# cpu_base.net
KiCad netlist of a schematic drawn in EAGLE
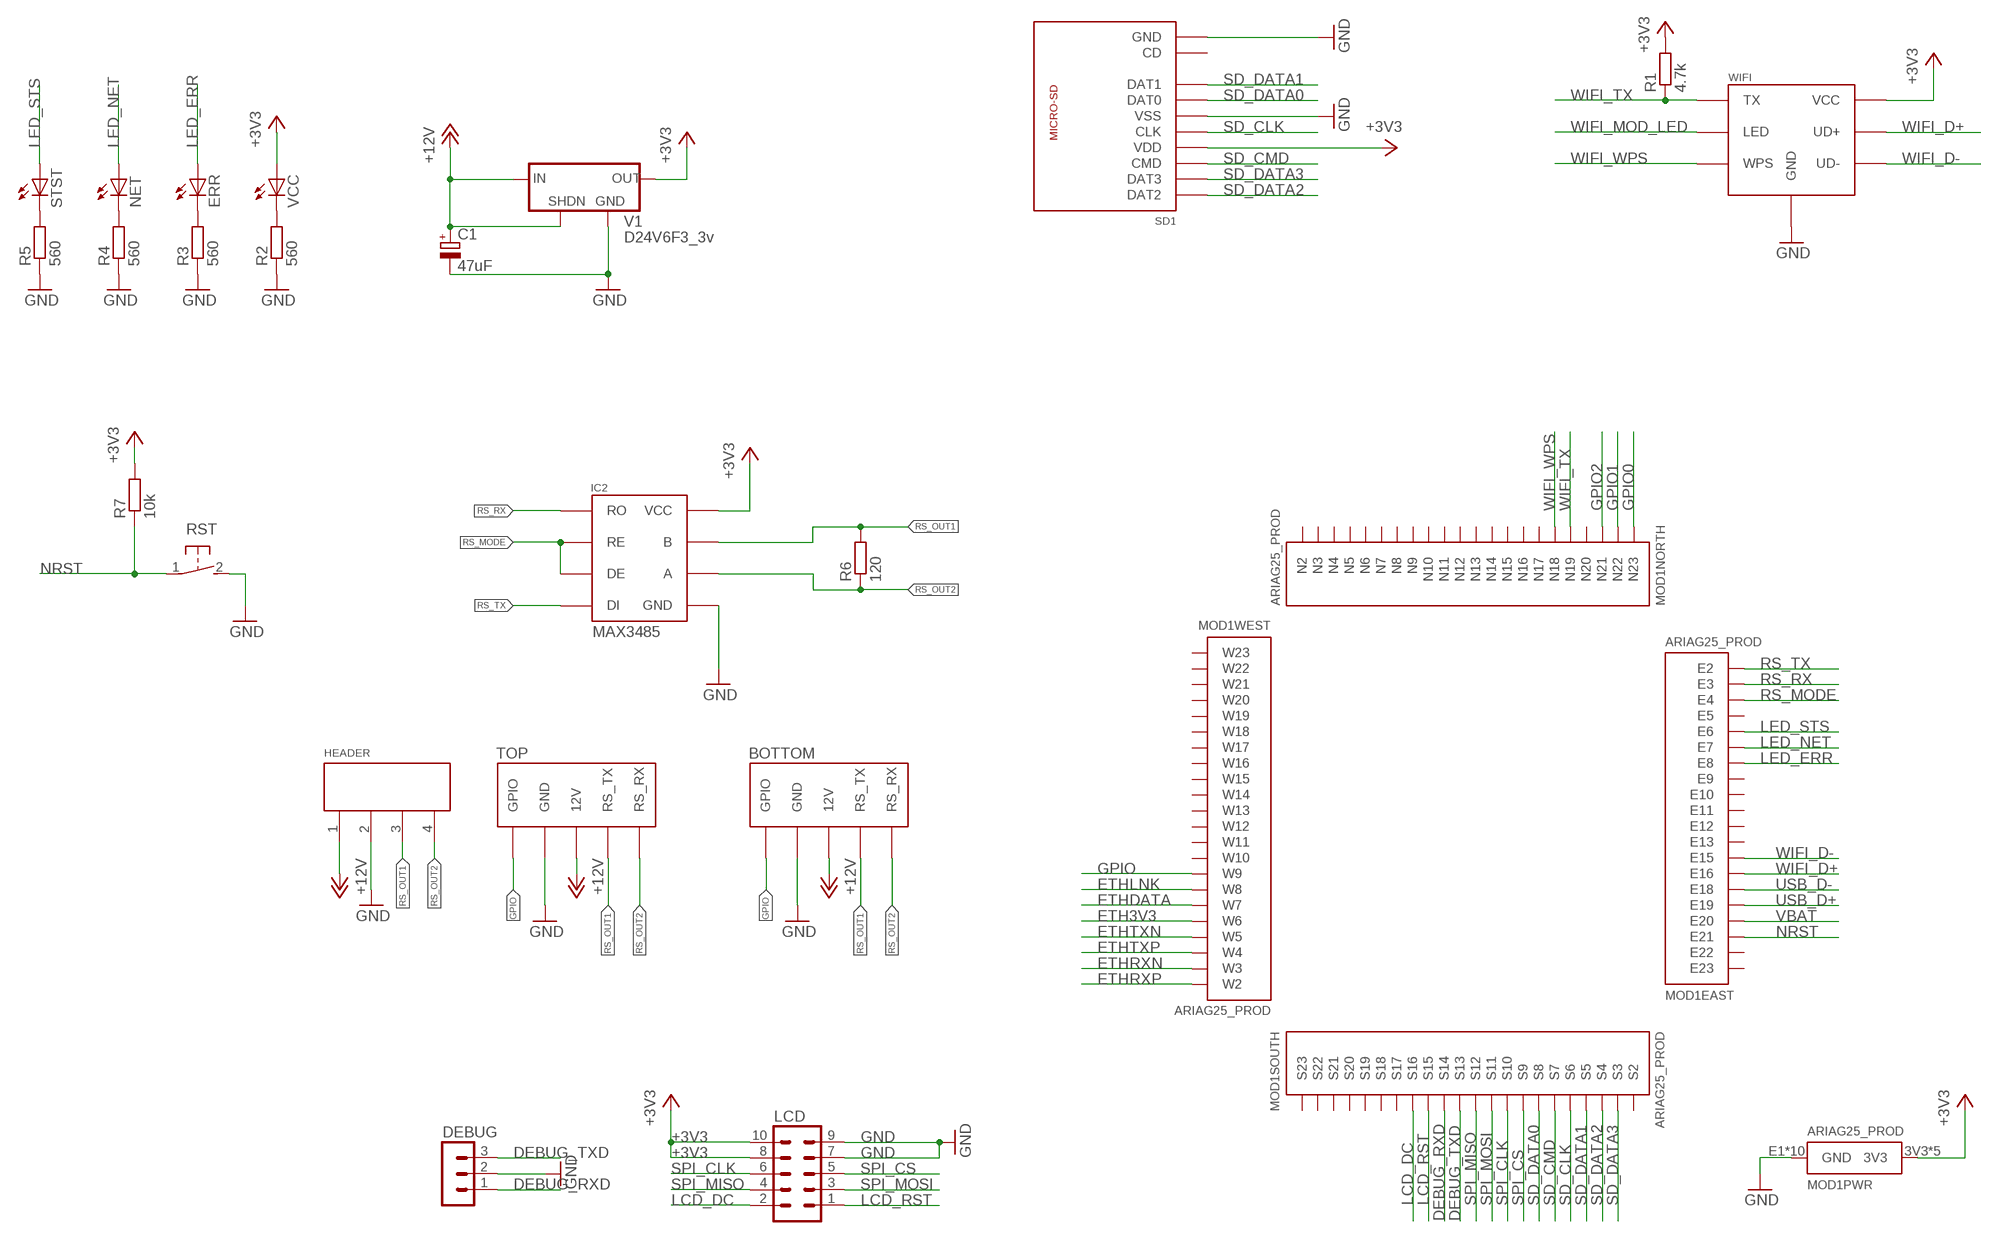
[diagram p0: schematic, sheet 1]

(export (version "E")
  (design (tool "Eeschema 10.0.6"))
  (components
    (comp (ref "BOTTOM")
      (value "STEROWNIK-PINY_5PIN_BOTTOM")
      (footprint "eagle-import:STEROWNIK-PINY_5PIN_BOTTOM")
      (libsource (lib "eagle-import") (part "STEROWNIK-PINY_5PIN_BOTTOM"))
    )
    (comp (ref "C1")
      (value "47uF")
      (footprint "eagle-import:153CLV-0810")
      (libsource (lib "eagle-import") (part "CPOL-EU153CLV-0810"))
    )
    (comp (ref "DEBUG")
      (value "MA03-1")
      (footprint "eagle-import:MA03-1")
      (libsource (lib "eagle-import") (part "MA03-1"))
    )
    (comp (ref "ERR")
      (value "LEDCHIPLED_0805")
      (footprint "eagle-import:CHIPLED_0805")
      (libsource (lib "eagle-import") (part "LEDCHIPLED_0805"))
    )
    (comp (ref "HEADER")
      (value "TBMP5104RO-KF")
      (footprint "eagle-import:TBMP5104RO-KF")
      (libsource (lib "eagle-import") (part "TBMP5104RO-KF"))
    )
    (comp (ref "IC2")
      (value "MAX3485")
      (footprint "eagle-import:SO-8")
      (libsource (lib "eagle-import") (part "MAX3485"))
    )
    (comp (ref "LCD")
      (value "MA05-2")
      (footprint "eagle-import:MA05-2")
      (libsource (lib "eagle-import") (part "MA05-2"))
    )
    (comp (ref "MOD1")
      (value "ARIAG25_PROD")
      (footprint "eagle-import:G25_D")
      (libsource (lib "eagle-import") (part "ARIAG25_PROD"))
    )
    (comp (ref "NET")
      (value "LEDCHIPLED_0805")
      (footprint "eagle-import:CHIPLED_0805")
      (libsource (lib "eagle-import") (part "LEDCHIPLED_0805"))
    )
    (comp (ref "R1")
      (value "4.7k")
      (footprint "eagle-import:R0805")
      (libsource (lib "eagle-import") (part "R-EU_R0805"))
    )
    (comp (ref "R2")
      (value "560")
      (footprint "eagle-import:R0805")
      (libsource (lib "eagle-import") (part "R-EU_R0805"))
    )
    (comp (ref "R3")
      (value "560")
      (footprint "eagle-import:R0805")
      (libsource (lib "eagle-import") (part "R-EU_R0805"))
    )
    (comp (ref "R4")
      (value "560")
      (footprint "eagle-import:R0805")
      (libsource (lib "eagle-import") (part "R-EU_R0805"))
    )
    (comp (ref "R5")
      (value "560")
      (footprint "eagle-import:R0805")
      (libsource (lib "eagle-import") (part "R-EU_R0805"))
    )
    (comp (ref "R6")
      (value "120")
      (footprint "eagle-import:R0805")
      (libsource (lib "eagle-import") (part "R-EU_R0805"))
    )
    (comp (ref "R7")
      (value "10k")
      (footprint "eagle-import:R0805")
      (libsource (lib "eagle-import") (part "R-EU_R0805"))
    )
    (comp (ref "RST")
      (value "31-XX")
      (footprint "eagle-import:B3F-31XX")
      (fields (field (name "MPN") "B3F-3100"))
      (libsource (lib "eagle-import") (part "31-XX"))
    )
    (comp (ref "SD1")
      (value "MICRO-SD")
      (footprint "eagle-import:112I-TDAR-R")
      (libsource (lib "eagle-import") (part "MICRO-SD"))
    )
    (comp (ref "STST")
      (value "LEDCHIPLED_0805")
      (footprint "eagle-import:CHIPLED_0805")
      (libsource (lib "eagle-import") (part "LEDCHIPLED_0805"))
    )
    (comp (ref "TOP")
      (value "STEROWNIK-PINY_5PIN")
      (footprint "eagle-import:STEROWNIK-PINY_5PIN")
      (libsource (lib "eagle-import") (part "STEROWNIK-PINY_5PIN"))
    )
    (comp (ref "V1")
      (value "D24V6F3_3v")
      (footprint "eagle-import:D24V6F5_5V")
      (libsource (lib "eagle-import") (part "D24V6F5_5V"))
    )
    (comp (ref "VCC")
      (value "LEDCHIPLED_0805")
      (footprint "eagle-import:CHIPLED_0805")
      (libsource (lib "eagle-import") (part "LEDCHIPLED_0805"))
    )
    (comp (ref "WIFI")
      (value "WIFI-2-OEM")
      (footprint "eagle-import:WIFI")
      (libsource (lib "eagle-import") (part "WIFI-2-OEM"))
    )
  )
  (nets
    (net (code "1") (name "+3V3") (class "Default")
      (node (ref "IC2") (pin "VCC") (pinfunction "VCC_VCC") (pintype "bidirectional"))
      (node (ref "LCD") (pin "10") (pinfunction "10_10") (pintype "passive"))
      (node (ref "LCD") (pin "8") (pinfunction "8_8") (pintype "passive"))
      (node (ref "MOD1") (pin "3V3") (pinfunction "3V3_3V3") (pintype "power_in"))
      (node (ref "MOD1") (pin "E24") (pinfunction "3V3_E24") (pintype "power_in"))
      (node (ref "MOD1") (pin "N1") (pinfunction "3V3_N1") (pintype "power_in"))
      (node (ref "MOD1") (pin "S1") (pinfunction "3V3_S1") (pintype "power_in"))
      (node (ref "MOD1") (pin "W24") (pinfunction "3V3_W24") (pintype "power_in"))
      (node (ref "R1") (pin "2") (pinfunction "2_2") (pintype "passive"))
      (node (ref "R7") (pin "2") (pinfunction "2_2") (pintype "passive"))
      (node (ref "SD1") (pin "4") (pinfunction "VDD_4") (pintype "bidirectional"))
      (node (ref "V1") (pin "VOUT") (pinfunction "OUT_VOUT") (pintype "passive"))
      (node (ref "VCC") (pin "A") (pinfunction "A_A") (pintype "passive"))
      (node (ref "WIFI") (pin "VCC") (pinfunction "VCC_VCC") (pintype "bidirectional"))
    )
    (net (code "2") (name "+12V") (class "Default")
      (node (ref "BOTTOM") (pin "12") (pinfunction "12V_12") (pintype "bidirectional"))
      (node (ref "C1") (pin "+") (pinfunction "+_+") (pintype "passive"))
      (node (ref "HEADER") (pin "1") (pinfunction "1_1") (pintype "bidirectional"))
      (node (ref "TOP") (pin "12V") (pinfunction "12V_12V") (pintype "bidirectional"))
      (node (ref "V1") (pin "SHDN") (pinfunction "SHDN_SHDN") (pintype "input"))
      (node (ref "V1") (pin "VIN") (pinfunction "IN_VIN") (pintype "input"))
    )
    (net (code "3") (name "DEBUG_RXD") (class "Default")
      (node (ref "DEBUG") (pin "1") (pinfunction "1_1") (pintype "passive"))
      (node (ref "MOD1") (pin "S14") (pinfunction "S14_S14") (pintype "bidirectional"))
    )
    (net (code "4") (name "DEBUG_TXD") (class "Default")
      (node (ref "DEBUG") (pin "3") (pinfunction "3_3") (pintype "passive"))
      (node (ref "MOD1") (pin "S13") (pinfunction "S13_S13") (pintype "bidirectional"))
    )
    (net (code "5") (name "ETH3V3") (class "Default")
      (node (ref "MOD1") (pin "W6") (pinfunction "W6_W6") (pintype "bidirectional"))
    )
    (net (code "6") (name "ETHDATA") (class "Default")
      (node (ref "MOD1") (pin "W7") (pinfunction "W7_W7") (pintype "bidirectional"))
    )
    (net (code "7") (name "ETHLNK") (class "Default")
      (node (ref "MOD1") (pin "W8") (pinfunction "W8_W8") (pintype "bidirectional"))
    )
    (net (code "8") (name "ETHRXN") (class "Default")
      (node (ref "MOD1") (pin "W3") (pinfunction "W3_W3") (pintype "bidirectional"))
    )
    (net (code "9") (name "ETHRXP") (class "Default")
      (node (ref "MOD1") (pin "W2") (pinfunction "W2_W2") (pintype "bidirectional"))
    )
    (net (code "10") (name "ETHTXN") (class "Default")
      (node (ref "MOD1") (pin "W5") (pinfunction "W5_W5") (pintype "bidirectional"))
    )
    (net (code "11") (name "ETHTXP") (class "Default")
      (node (ref "MOD1") (pin "W4") (pinfunction "W4_W4") (pintype "bidirectional"))
    )
    (net (code "12") (name "GND") (class "Default")
      (node (ref "BOTTOM") (pin "GND") (pinfunction "GND_GND") (pintype "bidirectional"))
      (node (ref "C1") (pin "-") (pinfunction "-_-") (pintype "passive"))
      (node (ref "DEBUG") (pin "2") (pinfunction "2_2") (pintype "passive"))
      (node (ref "HEADER") (pin "2") (pinfunction "2_2") (pintype "bidirectional"))
      (node (ref "IC2") (pin "GND") (pinfunction "GND_GND") (pintype "bidirectional"))
      (node (ref "LCD") (pin "7") (pinfunction "7_7") (pintype "passive"))
      (node (ref "LCD") (pin "9") (pinfunction "9_9") (pintype "passive"))
      (node (ref "MOD1") (pin "E1") (pinfunction "GND_E1") (pintype "power_in"))
      (node (ref "MOD1") (pin "E14") (pinfunction "GND_E14") (pintype "power_in"))
      (node (ref "MOD1") (pin "E17") (pinfunction "GND_E17") (pintype "power_in"))
      (node (ref "MOD1") (pin "GND@1") (pinfunction "GND_GND@1") (pintype "power_in"))
      (node (ref "MOD1") (pin "GND@2") (pinfunction "GND_GND@2") (pintype "power_in"))
      (node (ref "MOD1") (pin "GND@4") (pinfunction "GND_GND@4") (pintype "power_in"))
      (node (ref "MOD1") (pin "GND@5") (pinfunction "GND_GND@5") (pintype "power_in"))
      (node (ref "MOD1") (pin "N24") (pinfunction "GND_N24") (pintype "power_in"))
      (node (ref "MOD1") (pin "S24") (pinfunction "GND_S24") (pintype "power_in"))
      (node (ref "MOD1") (pin "W1") (pinfunction "GND_W1") (pintype "power_in"))
      (node (ref "R2") (pin "1") (pinfunction "1_1") (pintype "passive"))
      (node (ref "R3") (pin "1") (pinfunction "1_1") (pintype "passive"))
      (node (ref "R4") (pin "1") (pinfunction "1_1") (pintype "passive"))
      (node (ref "R5") (pin "1") (pinfunction "1_1") (pintype "passive"))
      (node (ref "RST") (pin "2") (pinfunction "S_2") (pintype "passive"))
      (node (ref "SD1") (pin "6") (pinfunction "VSS_6") (pintype "bidirectional"))
      (node (ref "SD1") (pin "GND_A") (pinfunction "GND_GND_A") (pintype "bidirectional"))
      (node (ref "SD1") (pin "GND_B") (pinfunction "GND_GND_B") (pintype "bidirectional"))
      (node (ref "SD1") (pin "GND_C") (pinfunction "GND_GND_C") (pintype "bidirectional"))
      (node (ref "TOP") (pin "GND") (pinfunction "GND_GND") (pintype "bidirectional"))
      (node (ref "V1") (pin "GND") (pinfunction "GND_GND") (pintype "input"))
      (node (ref "WIFI") (pin "GND") (pinfunction "GND_GND") (pintype "bidirectional"))
    )
    (net (code "13") (name "GPIO") (class "Default")
      (node (ref "BOTTOM") (pin "GPIO1") (pinfunction "GPIO_GPIO1") (pintype "bidirectional"))
      (node (ref "MOD1") (pin "W9") (pinfunction "W9_W9") (pintype "bidirectional"))
      (node (ref "TOP") (pin "GPIO1") (pinfunction "GPIO_GPIO1") (pintype "bidirectional"))
    )
    (net (code "14") (name "GPIO0") (class "Default")
      (node (ref "MOD1") (pin "N23") (pinfunction "N23_N23") (pintype "bidirectional"))
    )
    (net (code "15") (name "GPIO1") (class "Default")
      (node (ref "MOD1") (pin "N22") (pinfunction "N22_N22") (pintype "bidirectional"))
    )
    (net (code "16") (name "GPIO2") (class "Default")
      (node (ref "MOD1") (pin "N21") (pinfunction "N21_N21") (pintype "bidirectional"))
    )
    (net (code "17") (name "LCD_DC") (class "Default")
      (node (ref "LCD") (pin "2") (pinfunction "2_2") (pintype "passive"))
      (node (ref "MOD1") (pin "S16") (pinfunction "S16_S16") (pintype "bidirectional"))
    )
    (net (code "18") (name "LCD_RST") (class "Default")
      (node (ref "LCD") (pin "1") (pinfunction "1_1") (pintype "passive"))
      (node (ref "MOD1") (pin "S15") (pinfunction "S15_S15") (pintype "bidirectional"))
    )
    (net (code "19") (name "LED_ERR") (class "Default")
      (node (ref "ERR") (pin "A") (pinfunction "A_A") (pintype "passive"))
      (node (ref "MOD1") (pin "E8") (pinfunction "E8_E8") (pintype "bidirectional"))
    )
    (net (code "20") (name "LED_NET") (class "Default")
      (node (ref "MOD1") (pin "E7") (pinfunction "E7_E7") (pintype "bidirectional"))
      (node (ref "NET") (pin "A") (pinfunction "A_A") (pintype "passive"))
    )
    (net (code "21") (name "LED_STS") (class "Default")
      (node (ref "MOD1") (pin "E6") (pinfunction "E6_E6") (pintype "bidirectional"))
      (node (ref "STST") (pin "A") (pinfunction "A_A") (pintype "passive"))
    )
    (net (code "22") (name "NRST") (class "Default")
      (node (ref "MOD1") (pin "E21") (pinfunction "E21_E21") (pintype "bidirectional"))
      (node (ref "R7") (pin "1") (pinfunction "1_1") (pintype "passive"))
      (node (ref "RST") (pin "1") (pinfunction "P_1") (pintype "passive"))
    )
    (net (code "23") (name "Net-(ERR-PadC)") (class "Default")
      (node (ref "ERR") (pin "C") (pinfunction "C_C") (pintype "passive"))
      (node (ref "R3") (pin "2") (pinfunction "2_2") (pintype "passive"))
    )
    (net (code "24") (name "Net-(NET-PadC)") (class "Default")
      (node (ref "NET") (pin "C") (pinfunction "C_C") (pintype "passive"))
      (node (ref "R4") (pin "2") (pinfunction "2_2") (pintype "passive"))
    )
    (net (code "25") (name "Net-(R2-Pad2)") (class "Default")
      (node (ref "R2") (pin "2") (pinfunction "2_2") (pintype "passive"))
      (node (ref "VCC") (pin "C") (pinfunction "C_C") (pintype "passive"))
    )
    (net (code "26") (name "Net-(R5-Pad2)") (class "Default")
      (node (ref "R5") (pin "2") (pinfunction "2_2") (pintype "passive"))
      (node (ref "STST") (pin "C") (pinfunction "C_C") (pintype "passive"))
    )
    (net (code "27") (name "RS_MODE") (class "Default")
      (node (ref "IC2") (pin "DE") (pinfunction "DE_DE") (pintype "bidirectional"))
      (node (ref "IC2") (pin "RE") (pinfunction "RE_RE") (pintype "bidirectional"))
      (node (ref "MOD1") (pin "E4") (pinfunction "E4_E4") (pintype "bidirectional"))
    )
    (net (code "28") (name "RS_OUT1") (class "Default")
      (node (ref "BOTTOM") (pin "RS_TX") (pinfunction "RS_TX_RS_TX") (pintype "bidirectional"))
      (node (ref "HEADER") (pin "3") (pinfunction "3_3") (pintype "bidirectional"))
      (node (ref "IC2") (pin "B") (pinfunction "B_B") (pintype "bidirectional"))
      (node (ref "R6") (pin "2") (pinfunction "2_2") (pintype "passive"))
      (node (ref "TOP") (pin "RS_TX") (pinfunction "RS_TX_RS_TX") (pintype "bidirectional"))
    )
    (net (code "29") (name "RS_OUT2") (class "Default")
      (node (ref "BOTTOM") (pin "RS_RX") (pinfunction "RS_RX_RS_RX") (pintype "bidirectional"))
      (node (ref "HEADER") (pin "4") (pinfunction "4_4") (pintype "bidirectional"))
      (node (ref "IC2") (pin "A") (pinfunction "A_A") (pintype "bidirectional"))
      (node (ref "R6") (pin "1") (pinfunction "1_1") (pintype "passive"))
      (node (ref "TOP") (pin "RS_RX") (pinfunction "RS_RX_RS_RX") (pintype "bidirectional"))
    )
    (net (code "30") (name "RS_RX") (class "Default")
      (node (ref "IC2") (pin "RO") (pinfunction "RO_RO") (pintype "bidirectional"))
      (node (ref "MOD1") (pin "E3") (pinfunction "E3_E3") (pintype "bidirectional"))
    )
    (net (code "31") (name "RS_TX") (class "Default")
      (node (ref "IC2") (pin "DI") (pinfunction "DI_DI") (pintype "bidirectional"))
      (node (ref "MOD1") (pin "E2") (pinfunction "E2_E2") (pintype "bidirectional"))
    )
    (net (code "32") (name "SD_CLK") (class "Default")
      (node (ref "MOD1") (pin "S6") (pinfunction "S6_S6") (pintype "bidirectional"))
      (node (ref "SD1") (pin "5") (pinfunction "CLK_5") (pintype "bidirectional"))
    )
    (net (code "33") (name "SD_CMD") (class "Default")
      (node (ref "MOD1") (pin "S7") (pinfunction "S7_S7") (pintype "bidirectional"))
      (node (ref "SD1") (pin "3") (pinfunction "CMD_3") (pintype "bidirectional"))
    )
    (net (code "34") (name "SD_DATA0") (class "Default")
      (node (ref "MOD1") (pin "S8") (pinfunction "S8_S8") (pintype "bidirectional"))
      (node (ref "SD1") (pin "7") (pinfunction "DAT0_7") (pintype "bidirectional"))
    )
    (net (code "35") (name "SD_DATA1") (class "Default")
      (node (ref "MOD1") (pin "S5") (pinfunction "S5_S5") (pintype "bidirectional"))
      (node (ref "SD1") (pin "8") (pinfunction "DAT1_8") (pintype "bidirectional"))
    )
    (net (code "36") (name "SD_DATA2") (class "Default")
      (node (ref "MOD1") (pin "S4") (pinfunction "S4_S4") (pintype "bidirectional"))
      (node (ref "SD1") (pin "1") (pinfunction "DAT2_1") (pintype "bidirectional"))
    )
    (net (code "37") (name "SD_DATA3") (class "Default")
      (node (ref "MOD1") (pin "S3") (pinfunction "S3_S3") (pintype "bidirectional"))
      (node (ref "SD1") (pin "2") (pinfunction "DAT3_2") (pintype "bidirectional"))
    )
    (net (code "38") (name "SPI_CLK") (class "Default")
      (node (ref "LCD") (pin "6") (pinfunction "6_6") (pintype "passive"))
      (node (ref "MOD1") (pin "S10") (pinfunction "S10_S10") (pintype "bidirectional"))
    )
    (net (code "39") (name "SPI_CS") (class "Default")
      (node (ref "LCD") (pin "5") (pinfunction "5_5") (pintype "passive"))
      (node (ref "MOD1") (pin "S9") (pinfunction "S9_S9") (pintype "bidirectional"))
    )
    (net (code "40") (name "SPI_MISO") (class "Default")
      (node (ref "LCD") (pin "4") (pinfunction "4_4") (pintype "passive"))
      (node (ref "MOD1") (pin "S12") (pinfunction "S12_S12") (pintype "bidirectional"))
    )
    (net (code "41") (name "SPI_MOSI") (class "Default")
      (node (ref "LCD") (pin "3") (pinfunction "3_3") (pintype "passive"))
      (node (ref "MOD1") (pin "S11") (pinfunction "S11_S11") (pintype "bidirectional"))
    )
    (net (code "42") (name "USB_D+") (class "Default")
      (node (ref "MOD1") (pin "E19") (pinfunction "E19_E19") (pintype "bidirectional"))
    )
    (net (code "43") (name "USB_D-") (class "Default")
      (node (ref "MOD1") (pin "E18") (pinfunction "E18_E18") (pintype "bidirectional"))
    )
    (net (code "44") (name "VBAT") (class "Default")
      (node (ref "MOD1") (pin "E20") (pinfunction "E20_E20") (pintype "bidirectional"))
    )
    (net (code "45") (name "WIFI_D+") (class "Default")
      (node (ref "MOD1") (pin "E16") (pinfunction "E16_E16") (pintype "bidirectional"))
      (node (ref "WIFI") (pin "UD+") (pinfunction "UD+_UD+") (pintype "bidirectional"))
    )
    (net (code "46") (name "WIFI_D-") (class "Default")
      (node (ref "MOD1") (pin "E15") (pinfunction "E15_E15") (pintype "bidirectional"))
      (node (ref "WIFI") (pin "UD-") (pinfunction "UD-_UD-") (pintype "bidirectional"))
    )
    (net (code "47") (name "WIFI_MOD_LED") (class "Default")
      (node (ref "WIFI") (pin "LED") (pinfunction "LED_LED") (pintype "bidirectional"))
    )
    (net (code "48") (name "WIFI_TX") (class "Default")
      (node (ref "MOD1") (pin "N19") (pinfunction "N19_N19") (pintype "bidirectional"))
      (node (ref "R1") (pin "1") (pinfunction "1_1") (pintype "passive"))
      (node (ref "WIFI") (pin "TX") (pinfunction "TX_TX") (pintype "bidirectional"))
    )
    (net (code "49") (name "WIFI_WPS") (class "Default")
      (node (ref "MOD1") (pin "N18") (pinfunction "N18_N18") (pintype "bidirectional"))
      (node (ref "WIFI") (pin "WPS") (pinfunction "WPS_WPS") (pintype "bidirectional"))
    )
    (net (code "50") (name "unconnected-(MOD1-PadE5)") (class "Default")
      (node (ref "MOD1") (pin "E5") (pinfunction "E5_E5") (pintype "bidirectional"))
    )
    (net (code "51") (name "unconnected-(MOD1-PadE9)") (class "Default")
      (node (ref "MOD1") (pin "E9") (pinfunction "E9_E9") (pintype "bidirectional"))
    )
    (net (code "52") (name "unconnected-(MOD1-PadE10)") (class "Default")
      (node (ref "MOD1") (pin "E10") (pinfunction "E10_E10") (pintype "bidirectional"))
    )
    (net (code "53") (name "unconnected-(MOD1-PadE11)") (class "Default")
      (node (ref "MOD1") (pin "E11") (pinfunction "E11_E11") (pintype "bidirectional"))
    )
    (net (code "54") (name "unconnected-(MOD1-PadE12)") (class "Default")
      (node (ref "MOD1") (pin "E12") (pinfunction "E12_E12") (pintype "bidirectional"))
    )
    (net (code "55") (name "unconnected-(MOD1-PadE13)") (class "Default")
      (node (ref "MOD1") (pin "E13") (pinfunction "E13_E13") (pintype "bidirectional"))
    )
    (net (code "56") (name "unconnected-(MOD1-PadE22)") (class "Default")
      (node (ref "MOD1") (pin "E22") (pinfunction "E22_E22") (pintype "bidirectional"))
    )
    (net (code "57") (name "unconnected-(MOD1-PadE23)") (class "Default")
      (node (ref "MOD1") (pin "E23") (pinfunction "E23_E23") (pintype "bidirectional"))
    )
    (net (code "58") (name "unconnected-(MOD1-PadN2)") (class "Default")
      (node (ref "MOD1") (pin "N2") (pinfunction "N2_N2") (pintype "bidirectional"))
    )
    (net (code "59") (name "unconnected-(MOD1-PadN3)") (class "Default")
      (node (ref "MOD1") (pin "N3") (pinfunction "N3_N3") (pintype "bidirectional"))
    )
    (net (code "60") (name "unconnected-(MOD1-PadN4)") (class "Default")
      (node (ref "MOD1") (pin "N4") (pinfunction "N4_N4") (pintype "bidirectional"))
    )
    (net (code "61") (name "unconnected-(MOD1-PadN5)") (class "Default")
      (node (ref "MOD1") (pin "N5") (pinfunction "N5_N5") (pintype "bidirectional"))
    )
    (net (code "62") (name "unconnected-(MOD1-PadN6)") (class "Default")
      (node (ref "MOD1") (pin "N6") (pinfunction "N6_N6") (pintype "bidirectional"))
    )
    (net (code "63") (name "unconnected-(MOD1-PadN7)") (class "Default")
      (node (ref "MOD1") (pin "N7") (pinfunction "N7_N7") (pintype "bidirectional"))
    )
    (net (code "64") (name "unconnected-(MOD1-PadN8)") (class "Default")
      (node (ref "MOD1") (pin "N8") (pinfunction "N8_N8") (pintype "bidirectional"))
    )
    (net (code "65") (name "unconnected-(MOD1-PadN9)") (class "Default")
      (node (ref "MOD1") (pin "N9") (pinfunction "N9_N9") (pintype "bidirectional"))
    )
    (net (code "66") (name "unconnected-(MOD1-PadN10)") (class "Default")
      (node (ref "MOD1") (pin "N10") (pinfunction "N10_N10") (pintype "bidirectional"))
    )
    (net (code "67") (name "unconnected-(MOD1-PadN11)") (class "Default")
      (node (ref "MOD1") (pin "N11") (pinfunction "N11_N11") (pintype "bidirectional"))
    )
    (net (code "68") (name "unconnected-(MOD1-PadN12)") (class "Default")
      (node (ref "MOD1") (pin "N12") (pinfunction "N12_N12") (pintype "bidirectional"))
    )
    (net (code "69") (name "unconnected-(MOD1-PadN13)") (class "Default")
      (node (ref "MOD1") (pin "N13") (pinfunction "N13_N13") (pintype "bidirectional"))
    )
    (net (code "70") (name "unconnected-(MOD1-PadN14)") (class "Default")
      (node (ref "MOD1") (pin "N14") (pinfunction "N14_N14") (pintype "bidirectional"))
    )
    (net (code "71") (name "unconnected-(MOD1-PadN15)") (class "Default")
      (node (ref "MOD1") (pin "N15") (pinfunction "N15_N15") (pintype "bidirectional"))
    )
    (net (code "72") (name "unconnected-(MOD1-PadN16)") (class "Default")
      (node (ref "MOD1") (pin "N16") (pinfunction "N16_N16") (pintype "bidirectional"))
    )
    (net (code "73") (name "unconnected-(MOD1-PadN17)") (class "Default")
      (node (ref "MOD1") (pin "N17") (pinfunction "N17_N17") (pintype "bidirectional"))
    )
    (net (code "74") (name "unconnected-(MOD1-PadN20)") (class "Default")
      (node (ref "MOD1") (pin "N20") (pinfunction "N20_N20") (pintype "bidirectional"))
    )
    (net (code "75") (name "unconnected-(MOD1-PadS2)") (class "Default")
      (node (ref "MOD1") (pin "S2") (pinfunction "S2_S2") (pintype "bidirectional"))
    )
    (net (code "76") (name "unconnected-(MOD1-PadS17)") (class "Default")
      (node (ref "MOD1") (pin "S17") (pinfunction "S17_S17") (pintype "bidirectional"))
    )
    (net (code "77") (name "unconnected-(MOD1-PadS18)") (class "Default")
      (node (ref "MOD1") (pin "S18") (pinfunction "S18_S18") (pintype "bidirectional"))
    )
    (net (code "78") (name "unconnected-(MOD1-PadS19)") (class "Default")
      (node (ref "MOD1") (pin "S19") (pinfunction "S19_S19") (pintype "bidirectional"))
    )
    (net (code "79") (name "unconnected-(MOD1-PadS20)") (class "Default")
      (node (ref "MOD1") (pin "S20") (pinfunction "S20_S20") (pintype "bidirectional"))
    )
    (net (code "80") (name "unconnected-(MOD1-PadS21)") (class "Default")
      (node (ref "MOD1") (pin "S21") (pinfunction "S21_S21") (pintype "bidirectional"))
    )
    (net (code "81") (name "unconnected-(MOD1-PadS22)") (class "Default")
      (node (ref "MOD1") (pin "S22") (pinfunction "S22_S22") (pintype "bidirectional"))
    )
    (net (code "82") (name "unconnected-(MOD1-PadS23)") (class "Default")
      (node (ref "MOD1") (pin "S23") (pinfunction "S23_S23") (pintype "bidirectional"))
    )
    (net (code "83") (name "unconnected-(MOD1-PadW10)") (class "Default")
      (node (ref "MOD1") (pin "W10") (pinfunction "W10_W10") (pintype "bidirectional"))
    )
    (net (code "84") (name "unconnected-(MOD1-PadW11)") (class "Default")
      (node (ref "MOD1") (pin "W11") (pinfunction "W11_W11") (pintype "bidirectional"))
    )
    (net (code "85") (name "unconnected-(MOD1-PadW12)") (class "Default")
      (node (ref "MOD1") (pin "W12") (pinfunction "W12_W12") (pintype "bidirectional"))
    )
    (net (code "86") (name "unconnected-(MOD1-PadW13)") (class "Default")
      (node (ref "MOD1") (pin "W13") (pinfunction "W13_W13") (pintype "bidirectional"))
    )
    (net (code "87") (name "unconnected-(MOD1-PadW14)") (class "Default")
      (node (ref "MOD1") (pin "W14") (pinfunction "W14_W14") (pintype "bidirectional"))
    )
    (net (code "88") (name "unconnected-(MOD1-PadW15)") (class "Default")
      (node (ref "MOD1") (pin "W15") (pinfunction "W15_W15") (pintype "bidirectional"))
    )
    (net (code "89") (name "unconnected-(MOD1-PadW16)") (class "Default")
      (node (ref "MOD1") (pin "W16") (pinfunction "W16_W16") (pintype "bidirectional"))
    )
    (net (code "90") (name "unconnected-(MOD1-PadW17)") (class "Default")
      (node (ref "MOD1") (pin "W17") (pinfunction "W17_W17") (pintype "bidirectional"))
    )
    (net (code "91") (name "unconnected-(MOD1-PadW18)") (class "Default")
      (node (ref "MOD1") (pin "W18") (pinfunction "W18_W18") (pintype "bidirectional"))
    )
    (net (code "92") (name "unconnected-(MOD1-PadW19)") (class "Default")
      (node (ref "MOD1") (pin "W19") (pinfunction "W19_W19") (pintype "bidirectional"))
    )
    (net (code "93") (name "unconnected-(MOD1-PadW20)") (class "Default")
      (node (ref "MOD1") (pin "W20") (pinfunction "W20_W20") (pintype "bidirectional"))
    )
    (net (code "94") (name "unconnected-(MOD1-PadW21)") (class "Default")
      (node (ref "MOD1") (pin "W21") (pinfunction "W21_W21") (pintype "bidirectional"))
    )
    (net (code "95") (name "unconnected-(MOD1-PadW22)") (class "Default")
      (node (ref "MOD1") (pin "W22") (pinfunction "W22_W22") (pintype "bidirectional"))
    )
    (net (code "96") (name "unconnected-(MOD1-PadW23)") (class "Default")
      (node (ref "MOD1") (pin "W23") (pinfunction "W23_W23") (pintype "bidirectional"))
    )
    (net (code "97") (name "unconnected-(SD1-PadCD)") (class "Default")
      (node (ref "SD1") (pin "CD") (pinfunction "CD_CD") (pintype "bidirectional"))
    )
  )
)
